# Multiplier_channel.net
KiCad netlist of a schematic drawn in Altium Designer
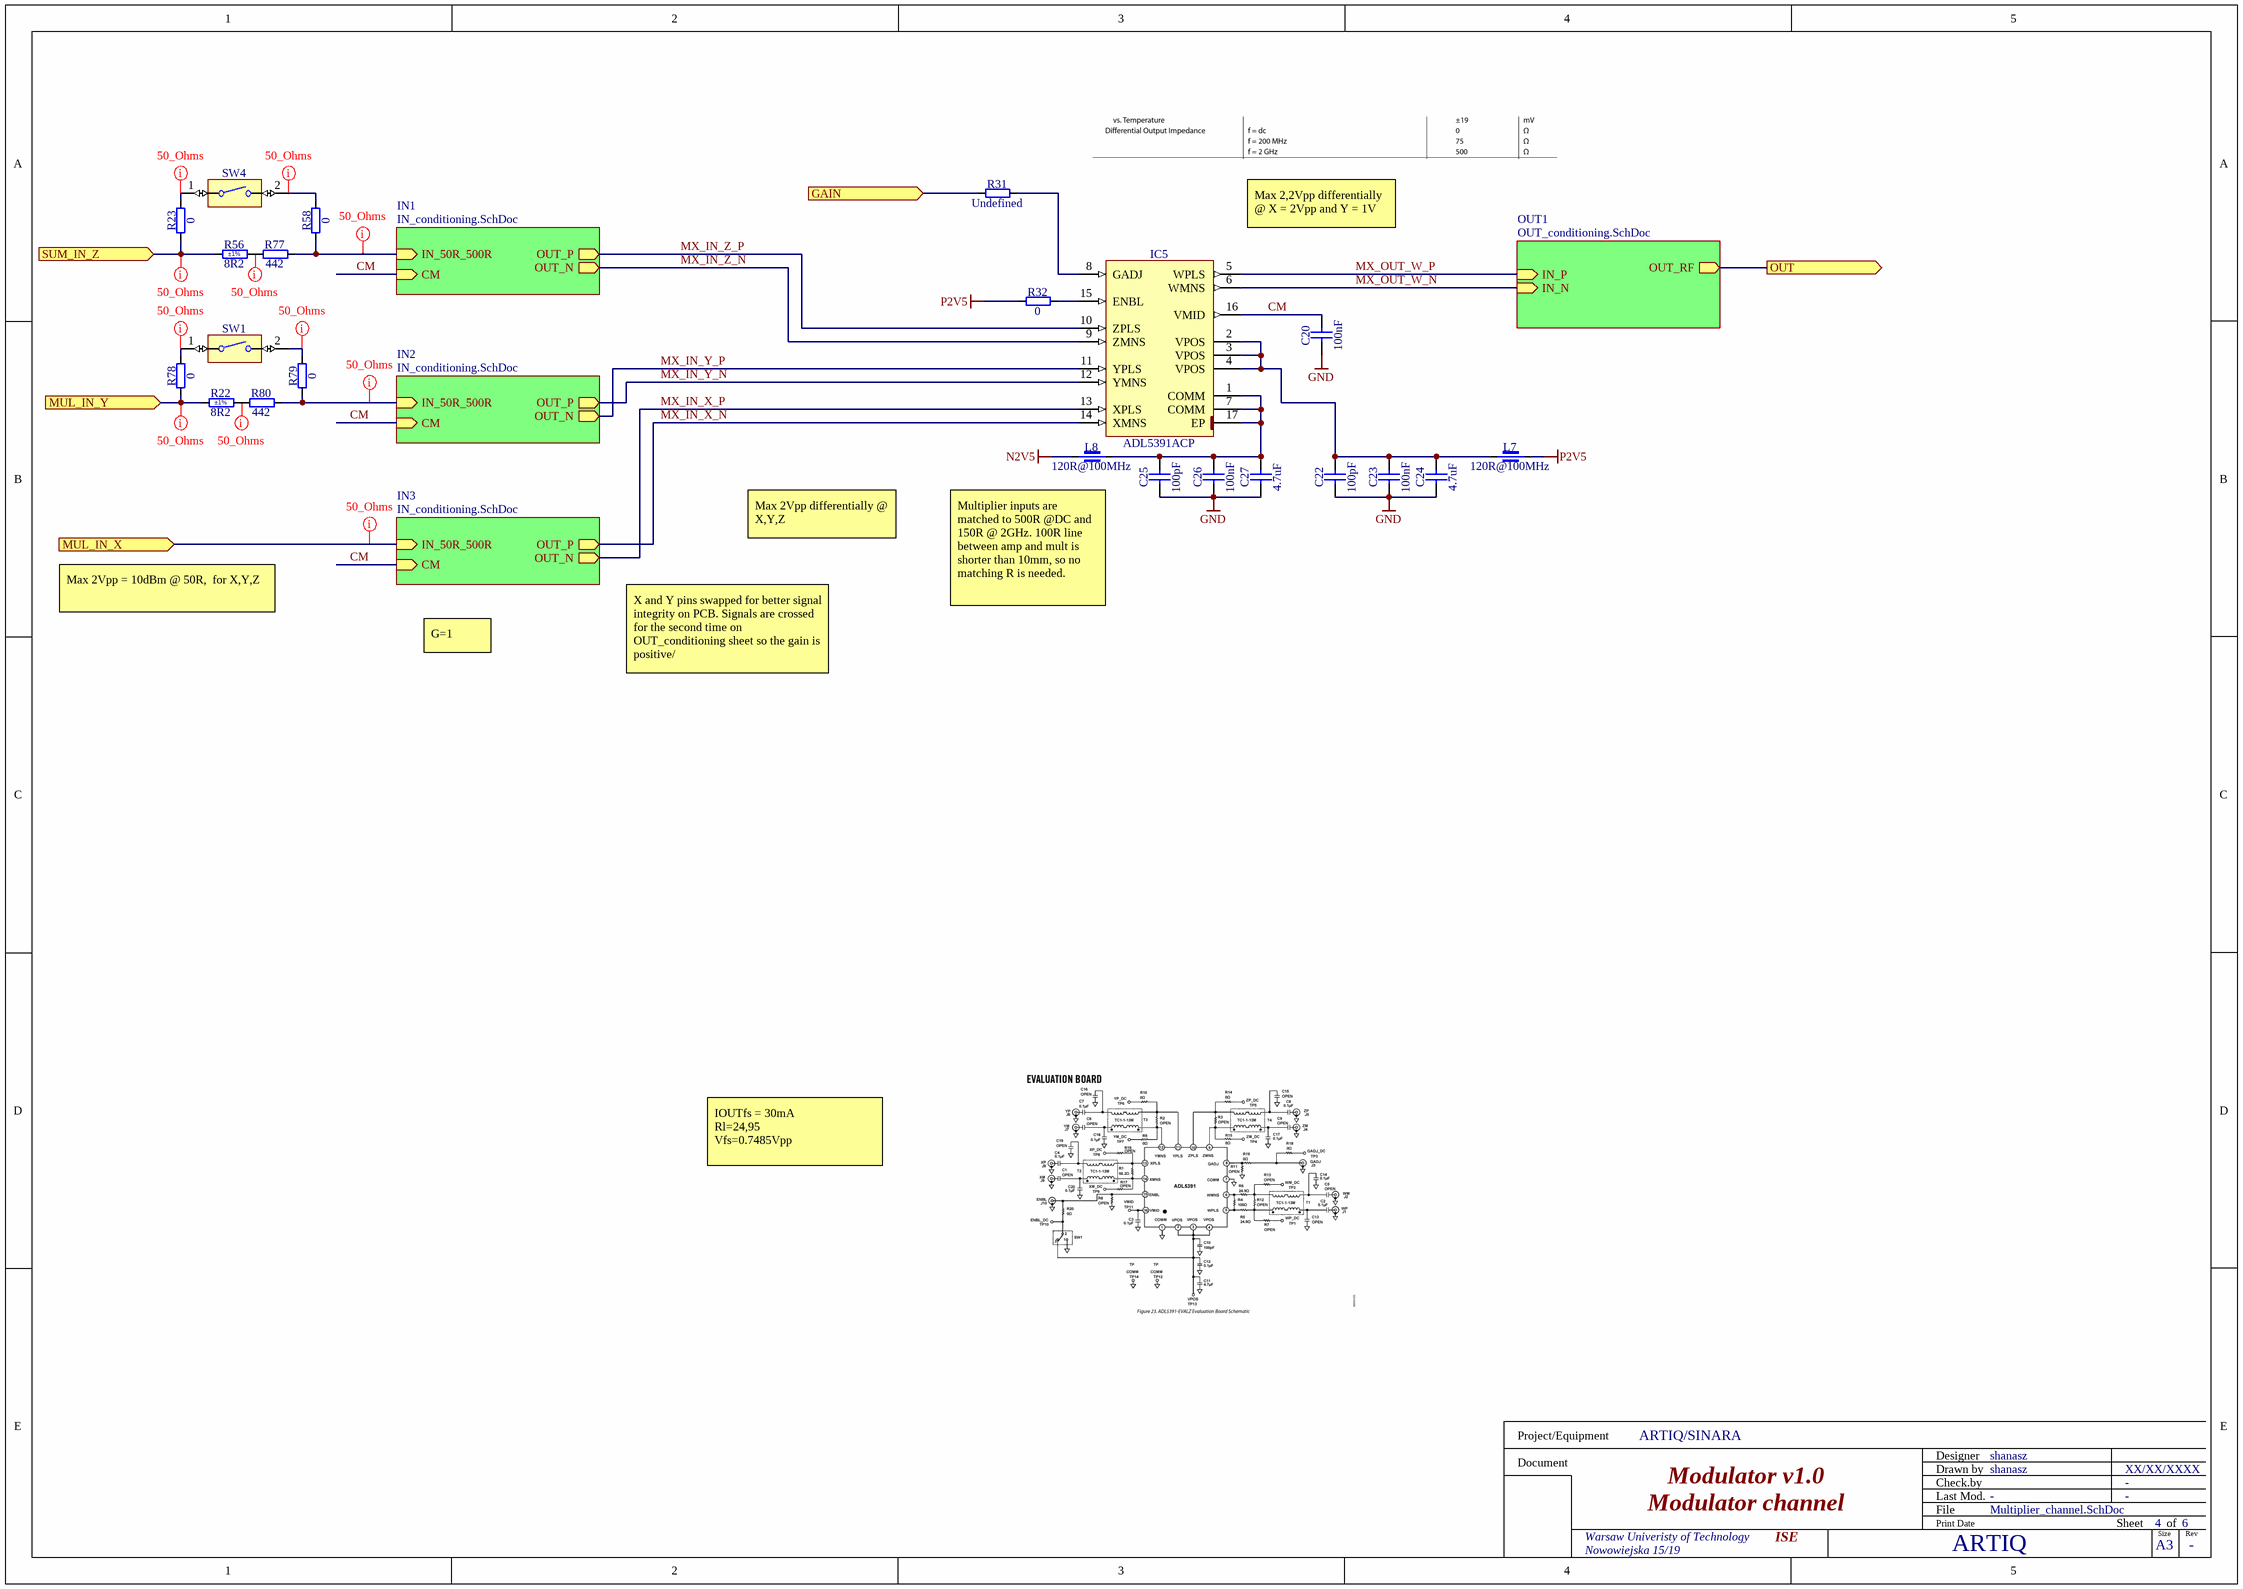
[diagram p0: Multiplier_channel.SchDoc]

(export (version "E")
  (design (tool "Eeschema 10.0.6"))
  (components
    (comp (ref "C20")
      (value "100nF")
      (footprint "CAPC1005X55N")
      (description "Non-polarised capacitor")
      (fields
        (field (name "PART NUMBER") "CC0402_100NF_16V_10%_X5R")
        (field (name "VOLTAGE") "16V")
        (field (name "AUTHOR") "CERN DEM JLC")
      )
      (libsource (lib "Capacitors") (part "Capacitor - non polarized"))
    )
    (comp (ref "C22")
      (value "100pF")
      (footprint "CAPC1005X55N")
      (description "Non-polarised capacitor")
      (fields
        (field (name "PART NUMBER") "CC0402_100PF_50V_2%_C0G")
        (field (name "VOLTAGE") "50V")
        (field (name "AUTHOR") "CERN DEM BC")
      )
      (libsource (lib "Capacitors") (part "Capacitor - non polarized"))
    )
    (comp (ref "C23")
      (value "100nF")
      (footprint "CAPC1005X55N")
      (description "Non-polarised capacitor")
      (fields
        (field (name "PART NUMBER") "CC0402_100NF_16V_10%_X5R")
        (field (name "VOLTAGE") "16V")
        (field (name "AUTHOR") "CERN DEM JLC")
      )
      (libsource (lib "Capacitors") (part "Capacitor - non polarized"))
    )
    (comp (ref "C24")
      (value "4.7uF")
      (footprint "CAPC1005X55N")
      (description "Non-polarised capacitor")
      (fields
        (field (name "PART NUMBER") "CC0402_4.7UF_4V_20%_X5R")
        (field (name "VOLTAGE") "4V")
        (field (name "AUTHOR") "CERN DEM JLC")
      )
      (libsource (lib "Capacitors") (part "Capacitor - non polarized"))
    )
    (comp (ref "C25")
      (value "100pF")
      (footprint "CAPC1005X55N")
      (description "Non-polarised capacitor")
      (fields
        (field (name "PART NUMBER") "CC0402_100PF_50V_2%_C0G")
        (field (name "VOLTAGE") "50V")
        (field (name "AUTHOR") "CERN DEM BC")
      )
      (libsource (lib "Capacitors") (part "Capacitor - non polarized"))
    )
    (comp (ref "C26")
      (value "100nF")
      (footprint "CAPC1005X55N")
      (description "Non-polarised capacitor")
      (fields
        (field (name "PART NUMBER") "CC0402_100NF_16V_10%_X5R")
        (field (name "VOLTAGE") "16V")
        (field (name "AUTHOR") "CERN DEM JLC")
      )
      (libsource (lib "Capacitors") (part "Capacitor - non polarized"))
    )
    (comp (ref "C27")
      (value "4.7uF")
      (footprint "CAPC1005X55N")
      (description "Non-polarised capacitor")
      (fields
        (field (name "PART NUMBER") "CC0402_4.7UF_4V_20%_X5R")
        (field (name "VOLTAGE") "4V")
        (field (name "AUTHOR") "CERN DEM JLC")
      )
      (libsource (lib "Capacitors") (part "Capacitor - non polarized"))
    )
    (comp (ref "IC5")
      (value "ADL5391ACP")
      (footprint "QFN50P300X300X100-17N-S145")
      (description "DC to 2.0 GHz Multiplier")
      (fields (field (name "MANUFACTURER") "ANALOG DEVICES") (field (name "AUTHOR") "CERN DEM HF"))
      (libsource (lib "Modulator_pLib") (part "ADL5391ACP"))
    )
    (comp (ref "L7")
      (value "120R@100MHz")
      (footprint "INDC1005X55N")
      (fields
        (field (name "PART NUMBER") "IND0402_MURATA_BLM15PX121SN1D")
        (field (name "POWER") "2A")
        (field (name "TOLERANCE") "±25%")
        (field (name "AUTHOR") "CERN DEM JMW")
      )
      (libsource (lib "Inductors & Transformers") (part "Ferrite Bead"))
    )
    (comp (ref "L8")
      (value "120R@100MHz")
      (footprint "INDC1005X55N")
      (fields
        (field (name "PART NUMBER") "IND0402_MURATA_BLM15PX121SN1D")
        (field (name "POWER") "2A")
        (field (name "TOLERANCE") "±25%")
        (field (name "AUTHOR") "CERN DEM JMW")
      )
      (libsource (lib "Inductors & Transformers") (part "Ferrite Bead"))
    )
    (comp (ref "R22")
      (value "8R2")
      (footprint "RESC1005X40N")
      (description "Resistor - 1%")
      (fields
        (field (name "TOLERANCE") "±1%")
        (field (name "PART NUMBER") "R0402_8R2_1%_0.0625W_200PPM")
        (field (name "POWER") "0.0625W")
        (field (name "AUTHOR") "CERN DEM JLC")
      )
      (libsource (lib "Resistors") (part "Resistor - 1%"))
    )
    (comp (ref "R23")
      (value "0")
      (footprint "RESC1005X40N")
      (description "Resistor")
      (fields
        (field (name "PART NUMBER") "R0402_0R_JUMPER")
        (field (name "MANUFACTURER") "GENERIC")
        (field (name "AUTHOR") "CERN DEM JLC")
      )
      (libsource (lib "Resistors") (part "Resistor"))
    )
    (comp (ref "R31")
      (value "Undefined")
      (footprint "RESC1005X40N")
      (description "Resistor")
      (fields (field (name "PART NUMBER") "R0402_NO-VALUE") (field (name "AUTHOR") "CERN DEM JLC"))
      (libsource (lib "Resistors") (part "Resistor"))
    )
    (comp (ref "R32")
      (value "0")
      (footprint "RESC1005X40N")
      (description "Resistor")
      (fields
        (field (name "PART NUMBER") "R0402_0R_JUMPER")
        (field (name "MANUFACTURER") "GENERIC")
        (field (name "AUTHOR") "CERN DEM JLC")
      )
      (libsource (lib "Resistors") (part "Resistor"))
    )
    (comp (ref "R56")
      (value "8R2")
      (footprint "RESC1005X40N")
      (description "Resistor - 1%")
      (fields
        (field (name "TOLERANCE") "±1%")
        (field (name "PART NUMBER") "R0402_8R2_1%_0.0625W_200PPM")
        (field (name "POWER") "0.0625W")
        (field (name "AUTHOR") "CERN DEM JLC")
      )
      (libsource (lib "Resistors") (part "Resistor - 1%"))
    )
    (comp (ref "R58")
      (value "0")
      (footprint "RESC1005X40N")
      (description "Resistor")
      (fields
        (field (name "PART NUMBER") "R0402_0R_JUMPER")
        (field (name "MANUFACTURER") "GENERIC")
        (field (name "AUTHOR") "CERN DEM JLC")
      )
      (libsource (lib "Resistors") (part "Resistor"))
    )
    (comp (ref "R77")
      (value "442")
      (footprint "RESC1005X40N")
      (description "Resistor - 0.1%")
      (fields
        (field (name "PART NUMBER") "R0402_442R_0.1%_0.063W_25PPM")
        (field (name "MANUFACTURER") "GENERIC")
        (field (name "AUTHOR") "SHA")
      )
      (libsource (lib "Modulator_pLib") (part "R0402_442R_0.1%_0.063W_25PPM"))
    )
    (comp (ref "R78")
      (value "0")
      (footprint "RESC1005X40N")
      (description "Resistor")
      (fields
        (field (name "PART NUMBER") "R0402_0R_JUMPER")
        (field (name "MANUFACTURER") "GENERIC")
        (field (name "AUTHOR") "CERN DEM JLC")
      )
      (libsource (lib "Resistors") (part "Resistor"))
    )
    (comp (ref "R79")
      (value "0")
      (footprint "RESC1005X40N")
      (description "Resistor")
      (fields
        (field (name "PART NUMBER") "R0402_0R_JUMPER")
        (field (name "MANUFACTURER") "GENERIC")
        (field (name "AUTHOR") "CERN DEM JLC")
      )
      (libsource (lib "Resistors") (part "Resistor"))
    )
    (comp (ref "R80")
      (value "442")
      (footprint "RESC1005X40N")
      (description "Resistor - 0.1%")
      (fields
        (field (name "PART NUMBER") "R0402_442R_0.1%_0.063W_25PPM")
        (field (name "MANUFACTURER") "GENERIC")
        (field (name "AUTHOR") "SHA")
      )
      (libsource (lib "Modulator_pLib") (part "R0402_442R_0.1%_0.063W_25PPM"))
    )
    (comp (ref "SW1")
      (value "Switch")
      (footprint "SW_OMRON_A6SN-1101")
      (description "1 Ways SPST DIP Switch")
      (fields
        (field (name "PART NUMBER") "SW_OMRON_A6SN-1101")
        (field (name "MANUFACTURER") "OMRON")
        (field (name "AUTHOR") "CERN DEM JLC")
      )
      (libsource (lib "Eletro-mechanical") (part "SW 1x SPST DIP Switch"))
    )
    (comp (ref "SW4")
      (value "Switch")
      (footprint "SW_OMRON_A6SN-1101")
      (description "1 Ways SPST DIP Switch")
      (fields
        (field (name "PART NUMBER") "SW_OMRON_A6SN-1101")
        (field (name "MANUFACTURER") "OMRON")
        (field (name "AUTHOR") "CERN DEM JLC")
      )
      (libsource (lib "Eletro-mechanical") (part "SW 1x SPST DIP Switch"))
    )
  )
  (nets
    (net (code "1") (name "/CM") (class "Default")
      (node (ref "C20") (pin "2") (pinfunction "2_2") (pintype "passive"))
      (node (ref "IC5") (pin "16") (pinfunction "VMID_16") (pintype "output"))
    )
    (net (code "2") (name "/GAIN") (class "Default")
      (node (ref "R31") (pin "1") (pinfunction "1_1") (pintype "passive"))
    )
    (net (code "3") (name "/IN_50R_500R") (class "Default")
      (node (ref "R79") (pin "1") (pinfunction "1_1") (pintype "passive"))
      (node (ref "R80") (pin "2") (pinfunction "2_2") (pintype "passive"))
    )
    (net (code "4") (name "/IN_50R_500R_1") (class "Default")
      (node (ref "R58") (pin "1") (pinfunction "1_1") (pintype "passive"))
      (node (ref "R77") (pin "2") (pinfunction "2_2") (pintype "passive"))
    )
    (net (code "6") (name "/MUL_IN_Y") (class "Default")
      (node (ref "R22") (pin "1") (pinfunction "1_1") (pintype "passive"))
      (node (ref "R78") (pin "1") (pinfunction "1_1") (pintype "passive"))
    )
    (net (code "7") (name "/MX_IN_X_N") (class "Default")
      (node (ref "IC5") (pin "14") (pinfunction "XMNS_14") (pintype "input"))
    )
    (net (code "8") (name "/MX_IN_X_P") (class "Default")
      (node (ref "IC5") (pin "13") (pinfunction "XPLS_13") (pintype "input"))
    )
    (net (code "9") (name "/MX_IN_Y_N") (class "Default")
      (node (ref "IC5") (pin "12") (pinfunction "YMNS_12") (pintype "input"))
    )
    (net (code "10") (name "/MX_IN_Y_P") (class "Default")
      (node (ref "IC5") (pin "11") (pinfunction "YPLS_11") (pintype "input"))
    )
    (net (code "11") (name "/MX_IN_Z_N") (class "Default")
      (node (ref "IC5") (pin "9") (pinfunction "ZMNS_9") (pintype "input"))
    )
    (net (code "12") (name "/MX_IN_Z_P") (class "Default")
      (node (ref "IC5") (pin "10") (pinfunction "ZPLS_10") (pintype "input"))
    )
    (net (code "13") (name "/MX_OUT_W_N") (class "Default")
      (node (ref "IC5") (pin "6") (pinfunction "WMNS_6") (pintype "output"))
    )
    (net (code "14") (name "/MX_OUT_W_P") (class "Default")
      (node (ref "IC5") (pin "5") (pinfunction "WPLS_5") (pintype "output"))
    )
    (net (code "16") (name "/SUM_IN_Z") (class "Default")
      (node (ref "R23") (pin "1") (pinfunction "1_1") (pintype "passive"))
      (node (ref "R56") (pin "1") (pinfunction "1_1") (pintype "passive"))
    )
    (net (code "17") (name "GND") (class "Default")
      (node (ref "C20") (pin "1") (pinfunction "1_1") (pintype "passive"))
      (node (ref "C22") (pin "1") (pinfunction "1_1") (pintype "passive"))
      (node (ref "C23") (pin "1") (pinfunction "1_1") (pintype "passive"))
      (node (ref "C24") (pin "1") (pinfunction "1_1") (pintype "passive"))
      (node (ref "C25") (pin "1") (pinfunction "1_1") (pintype "passive"))
      (node (ref "C26") (pin "1") (pinfunction "1_1") (pintype "passive"))
      (node (ref "C27") (pin "1") (pinfunction "1_1") (pintype "passive"))
    )
    (net (code "18") (name "N2V5") (class "Default")
      (node (ref "L8") (pin "1") (pinfunction "1_1") (pintype "passive"))
    )
    (net (code "19") (name "Net-(C22-Pad2)") (class "Default")
      (node (ref "C22") (pin "2") (pinfunction "2_2") (pintype "passive"))
      (node (ref "C23") (pin "2") (pinfunction "2_2") (pintype "passive"))
      (node (ref "C24") (pin "2") (pinfunction "2_2") (pintype "passive"))
      (node (ref "IC5") (pin "2") (pinfunction "VPOS_2") (pintype "power_in"))
      (node (ref "IC5") (pin "3") (pinfunction "VPOS_3") (pintype "power_in"))
      (node (ref "IC5") (pin "4") (pinfunction "VPOS_4") (pintype "power_in"))
      (node (ref "L7") (pin "1") (pinfunction "1_1") (pintype "passive"))
    )
    (net (code "20") (name "Net-(IC5-ENBL)") (class "Default")
      (node (ref "IC5") (pin "15") (pinfunction "ENBL_15") (pintype "input"))
      (node (ref "R32") (pin "2") (pinfunction "2_2") (pintype "passive"))
    )
    (net (code "21") (name "Net-(IC5-EP)") (class "Default")
      (node (ref "C25") (pin "2") (pinfunction "2_2") (pintype "passive"))
      (node (ref "C26") (pin "2") (pinfunction "2_2") (pintype "passive"))
      (node (ref "C27") (pin "2") (pinfunction "2_2") (pintype "passive"))
      (node (ref "IC5") (pin "1") (pinfunction "COMM_1") (pintype "power_in"))
      (node (ref "IC5") (pin "17") (pinfunction "EP_17") (pintype "power_in"))
      (node (ref "IC5") (pin "7") (pinfunction "COMM_7") (pintype "power_in"))
      (node (ref "L8") (pin "2") (pinfunction "2_2") (pintype "passive"))
    )
    (net (code "22") (name "Net-(IC5-GADJ)") (class "Default")
      (node (ref "IC5") (pin "8") (pinfunction "GADJ_8") (pintype "input"))
      (node (ref "R31") (pin "2") (pinfunction "2_2") (pintype "passive"))
    )
    (net (code "23") (name "Net-(R22-Pad2)") (class "Default")
      (node (ref "R22") (pin "2") (pinfunction "2_2") (pintype "passive"))
      (node (ref "R80") (pin "1") (pinfunction "1_1") (pintype "passive"))
    )
    (net (code "24") (name "Net-(R23-Pad2)") (class "Default")
      (node (ref "R23") (pin "2") (pinfunction "2_2") (pintype "passive"))
      (node (ref "SW4") (pin "1") (pinfunction "1_1") (pintype "bidirectional"))
    )
    (net (code "25") (name "Net-(R56-Pad2)") (class "Default")
      (node (ref "R56") (pin "2") (pinfunction "2_2") (pintype "passive"))
      (node (ref "R77") (pin "1") (pinfunction "1_1") (pintype "passive"))
    )
    (net (code "26") (name "Net-(R58-Pad2)") (class "Default")
      (node (ref "R58") (pin "2") (pinfunction "2_2") (pintype "passive"))
      (node (ref "SW4") (pin "2") (pinfunction "2_2") (pintype "bidirectional"))
    )
    (net (code "27") (name "Net-(R78-Pad2)") (class "Default")
      (node (ref "R78") (pin "2") (pinfunction "2_2") (pintype "passive"))
      (node (ref "SW1") (pin "1") (pinfunction "1_1") (pintype "bidirectional"))
    )
    (net (code "28") (name "Net-(R79-Pad2)") (class "Default")
      (node (ref "R79") (pin "2") (pinfunction "2_2") (pintype "passive"))
      (node (ref "SW1") (pin "2") (pinfunction "2_2") (pintype "bidirectional"))
    )
    (net (code "29") (name "P2V5") (class "Default")
      (node (ref "L7") (pin "2") (pinfunction "2_2") (pintype "passive"))
      (node (ref "R32") (pin "1") (pinfunction "1_1") (pintype "passive"))
    )
  )
)
